# speedPulser.net
KiCad netlist of a schematic drawn in EasyEDA Pro
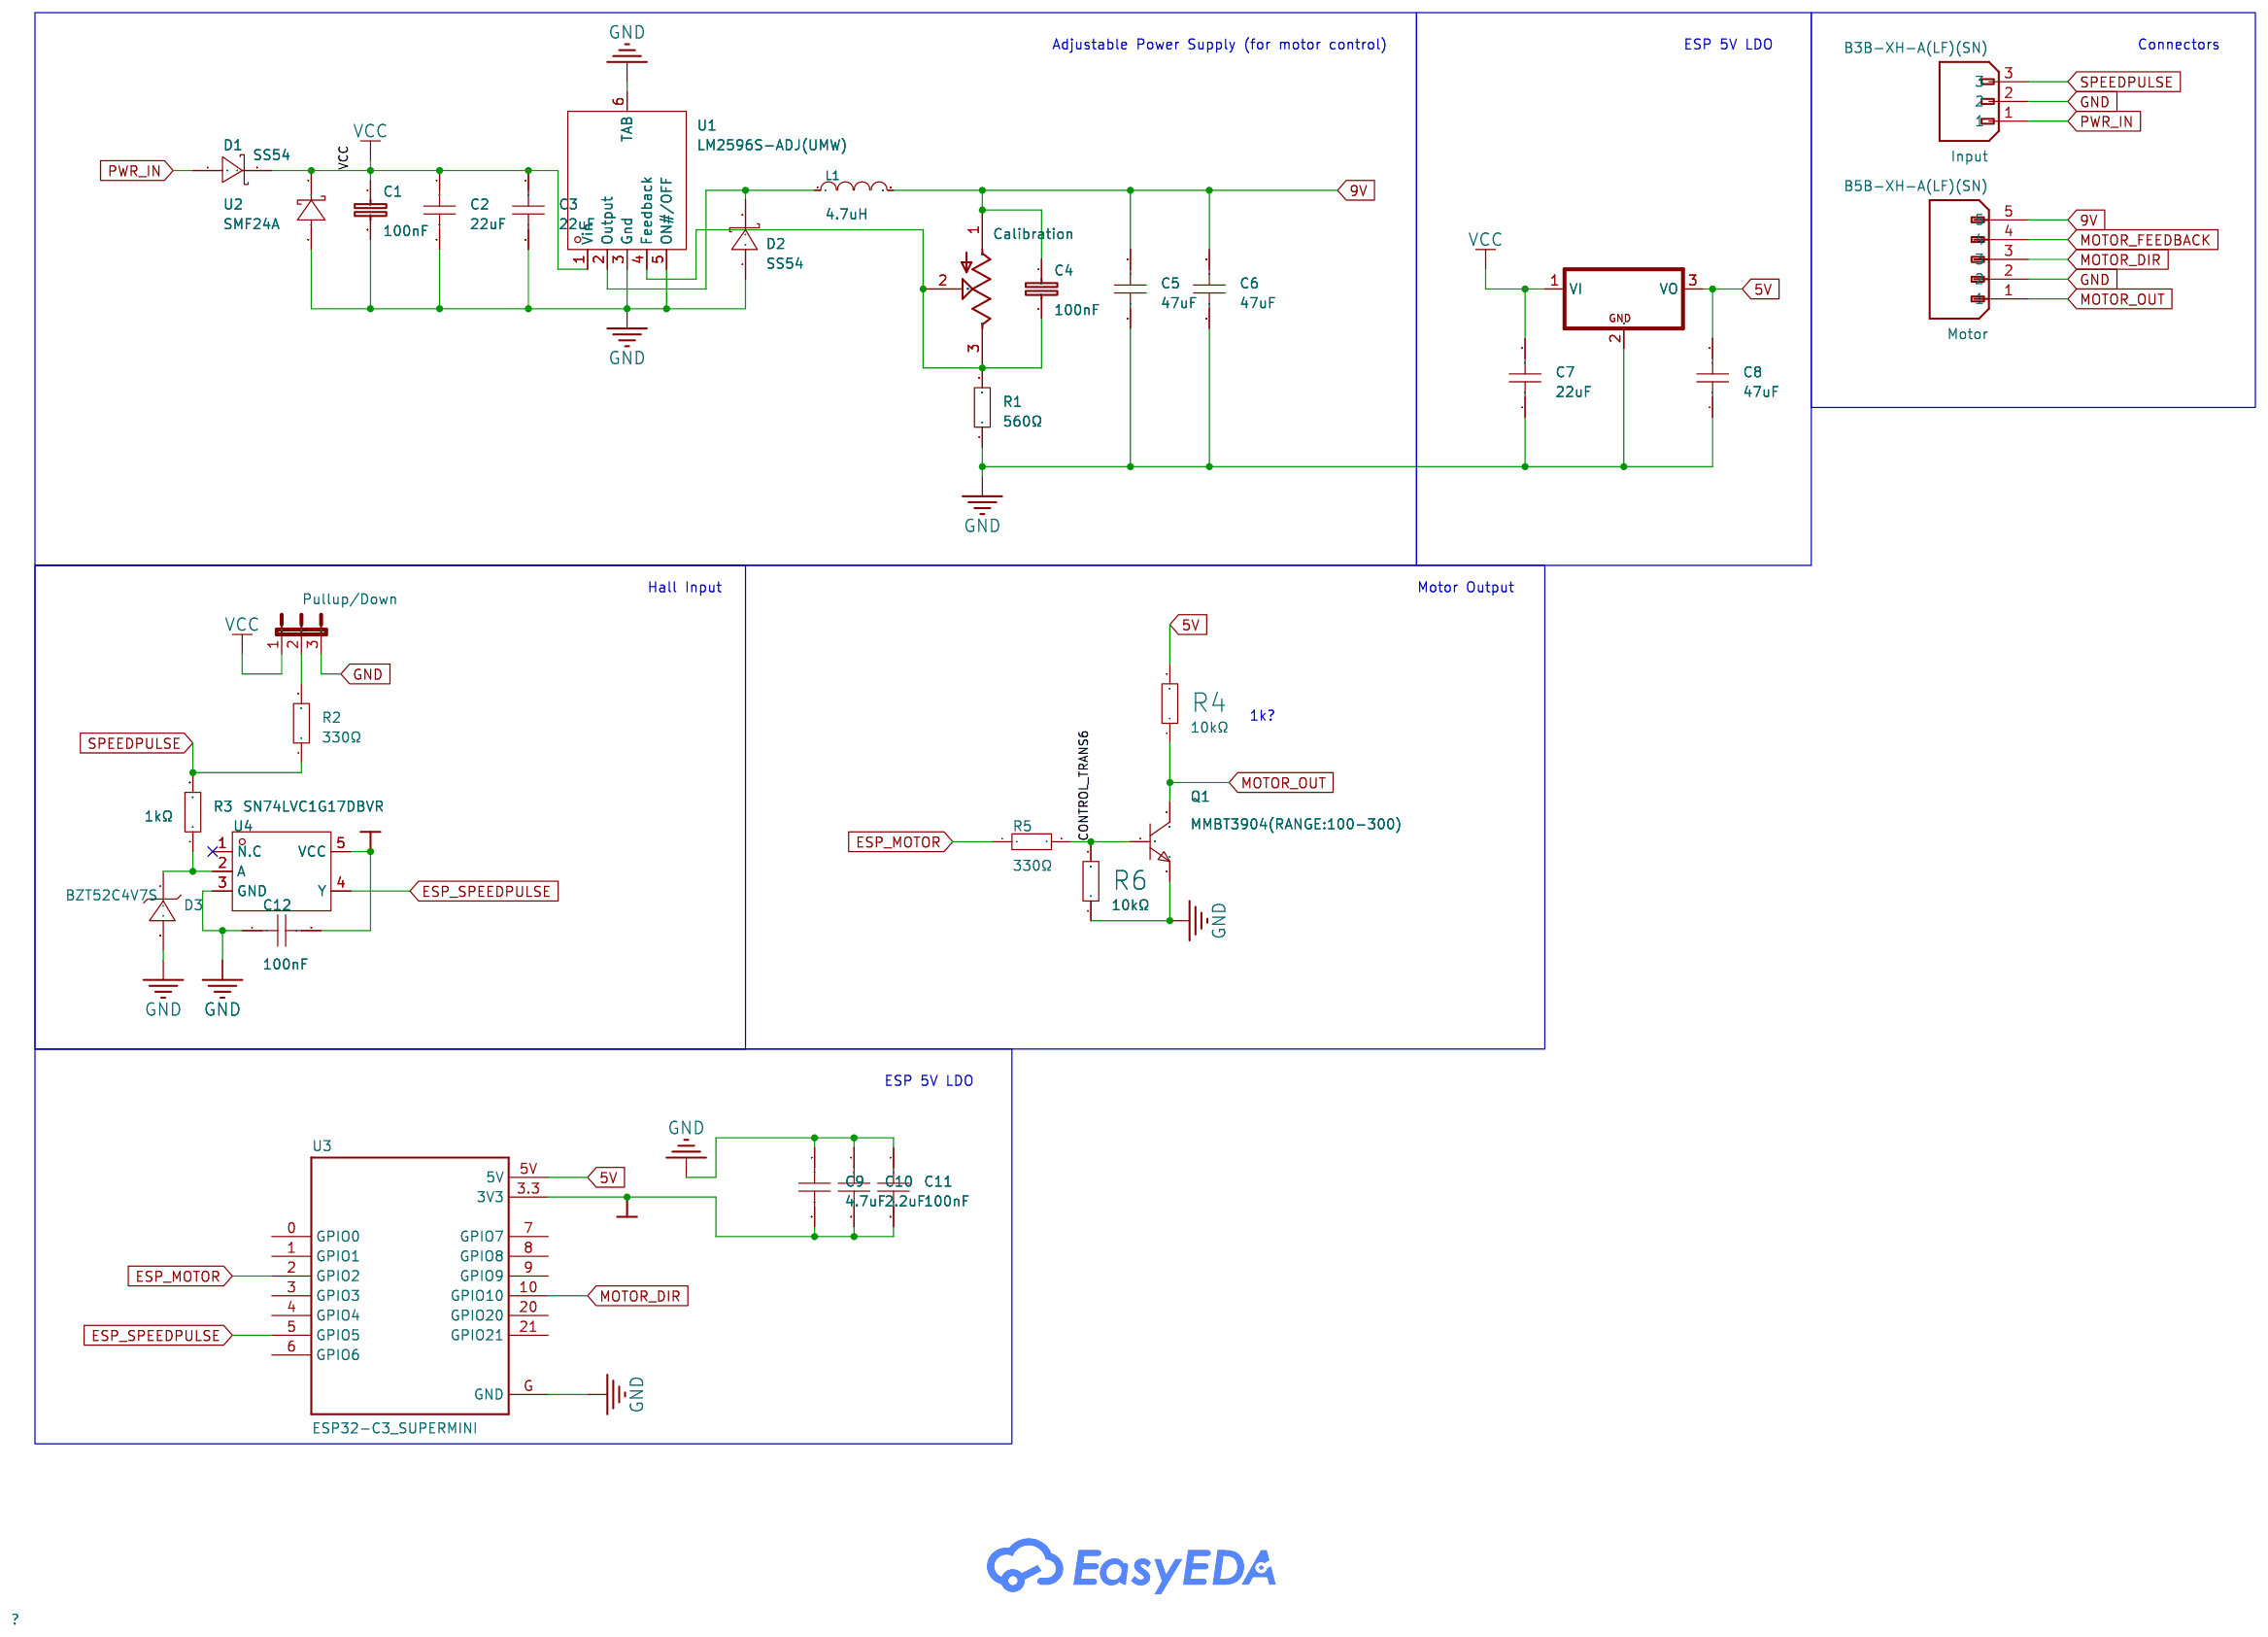
[diagram p0: schematic sheet]

(export (version "E")
  (design (tool "Eeschema 10.0.6"))
  (components
    (comp (ref "C1")
      (value "100nF")
      (description "Capacitance:100nF Tolerance:±10% Tolerance:±10% Voltage Rating:50V Temperature Coefficient:-")
      (fields
        (field (name "Manufacturer Part") "CT41G-0805-2X1-50V-0.1μF-K(N)")
        (field (name "Manufacturer") "TORCH(火炬)")
      )
      (libsource (lib "easyedapro") (part "capacitor-wima_C_2.5/2"))
    )
    (comp (ref "C2")
      (value "22uF")
      (footprint "easyedapro:C0805")
      (fields
        (field (name "Manufacturer Part") "HGC0805R5226M350NSLJ")
        (field (name "Manufacturer") "Chinocera(华瓷)")
      )
      (libsource (lib "easyedapro") (part "HGC0805R5226M350NSLJ"))
    )
    (comp (ref "C3")
      (value "22uF")
      (footprint "easyedapro:C0805")
      (fields
        (field (name "Manufacturer Part") "HGC0805R5226M350NSLJ")
        (field (name "Manufacturer") "Chinocera(华瓷)")
      )
      (libsource (lib "easyedapro") (part "HGC0805R5226M350NSLJ"))
    )
    (comp (ref "C4")
      (value "100nF")
      (description "Capacitance:100nF Tolerance:±10% Tolerance:±10% Voltage Rating:50V Temperature Coefficient:-")
      (fields
        (field (name "Manufacturer Part") "CT41G-0805-2X1-50V-0.1μF-K(N)")
        (field (name "Manufacturer") "TORCH(火炬)")
      )
      (libsource (lib "easyedapro") (part "capacitor-wima_C_2.5/2"))
    )
    (comp (ref "C5")
      (value "47uF")
      (footprint "easyedapro:C0805")
      (description "Capacitance:47uF Tolerance:±20% Tolerance:±20% Voltage Rating:10V Temperature Coefficient:X5R")
      (fields
        (field (name "Manufacturer Part") "CL21A476MPYNNWE")
        (field (name "Manufacturer") "SAMSUNG(三星)")
      )
      (libsource (lib "easyedapro") (part "CL21A476MPYNNWE"))
    )
    (comp (ref "C6")
      (value "47uF")
      (footprint "easyedapro:C0805")
      (description "Capacitance:47uF Tolerance:±20% Tolerance:±20% Voltage Rating:10V Temperature Coefficient:X5R")
      (fields
        (field (name "Manufacturer Part") "CL21A476MPYNNWE")
        (field (name "Manufacturer") "SAMSUNG(三星)")
      )
      (libsource (lib "easyedapro") (part "CL21A476MPYNNWE"))
    )
    (comp (ref "C7")
      (value "22uF")
      (footprint "easyedapro:C0805")
      (fields
        (field (name "Manufacturer Part") "HGC0805R5226M350NSLJ")
        (field (name "Manufacturer") "Chinocera(华瓷)")
      )
      (libsource (lib "easyedapro") (part "HGC0805R5226M350NSLJ"))
    )
    (comp (ref "C8")
      (value "47uF")
      (footprint "easyedapro:C0805")
      (description "Capacitance:47uF Tolerance:±20% Tolerance:±20% Voltage Rating:10V Temperature Coefficient:X5R")
      (fields
        (field (name "Manufacturer Part") "CL21A476MPYNNWE")
        (field (name "Manufacturer") "SAMSUNG(三星)")
      )
      (libsource (lib "easyedapro") (part "CL21A476MPYNNWE"))
    )
    (comp (ref "C9")
      (value "4.7uF")
      (description "Capacitance:4.7uF Tolerance:±10% Tolerance:±10% Voltage Rating:10V Temperature Coefficient:X5R")
      (fields
        (field (name "Manufacturer Part") "CL10A475KP8NNNC")
        (field (name "Manufacturer") "SAMSUNG(三星)")
      )
      (libsource (lib "easyedapro") (part "CAP"))
    )
    (comp (ref "C10")
      (value "2.2uF")
      (description "Capacitance:2.2uF Tolerance:±10% Tolerance:±10% Voltage Rating:16V Temperature Coefficient:X5R")
      (fields
        (field (name "Manufacturer Part") "CL10A225KO8NNNC")
        (field (name "Manufacturer") "SAMSUNG(三星)")
      )
      (libsource (lib "easyedapro") (part "CAP"))
    )
    (comp (ref "C11")
      (value "100nF")
      (description "Capacitance:100nF Tolerance:±10% Tolerance:±10% Voltage Rating:50V Temperature Coefficient:X7R")
      (fields
        (field (name "Manufacturer Part") "CL10B104KB8NNNC")
        (field (name "Manufacturer") "SAMSUNG(三星)")
      )
      (libsource (lib "easyedapro") (part "CAP"))
    )
    (comp (ref "C12")
      (value "100nF")
      (footprint "easyedapro:C0603")
      (description "Capacitance:100nF Tolerance:±10% Tolerance:±10% Voltage Rating:50V Temperature Coefficient:X7R")
      (fields
        (field (name "Manufacturer Part") "CC0603KRX7R9BB104")
        (field (name "Manufacturer") "YAGEO(国巨)")
      )
      (libsource (lib "easyedapro") (part "CC0603KRX7R9BB104"))
    )
    (comp (ref "Calibration")
      (value "10kΩ")
      (description "Resistance: Tolerance:±10% Tolerance:±10%")
      (fields (field (name "Manufacturer Part") "3362P-1-103") (field (name "Manufacturer") "BOCHEN(博晨)"))
      (libsource (lib "easyedapro") (part "3362P-1-253LF_3362P-1-253LF_"))
    )
    (comp (ref "D1")
      (value "SS54")
      (footprint "easyedapro:SMA_L4.4-W2.8-LS5.4-R-RD")
      (fields (field (name "Manufacturer") "MDD(辰达半导体)"))
      (libsource (lib "easyedapro") (part "SS54_C22452"))
    )
    (comp (ref "D2")
      (value "SS54")
      (footprint "easyedapro:SMA_L4.4-W2.8-LS5.4-R-RD")
      (fields (field (name "Manufacturer") "MDD(辰达半导体)"))
      (libsource (lib "easyedapro") (part "SS54_C22452"))
    )
    (comp (ref "D3")
      (value "BZT52C4V7S")
      (footprint "easyedapro:SOD-323_L1.8-W1.3-LS2.5-RD")
      (fields (field (name "Manufacturer") "晶导微电子"))
      (libsource (lib "easyedapro") (part "BZT52C4V7S_C353517"))
    )
    (comp (ref "IC1")
      (value "L7805ABD2T-TR")
      (fields (field (name "Manufacturer") "ST(意法半导体)"))
      (libsource (lib "easyedapro") (part "linear_78*_TV"))
    )
    (comp (ref "Input")
      (value "B3B-XH-A(LF)(SN)")
      (fields (field (name "Manufacturer") "JST"))
      (libsource (lib "easyedapro") (part "B3B-XH-A_LF__SN__B3B-XH-A(LF)(SN)_"))
    )
    (comp (ref "L1")
      (value "4.7uH")
      (footprint "easyedapro:IND-SMD_L4.8-W4.5")
      (fields (field (name "Manufacturer Part") "SMMS0420-4R7M") (field (name "Manufacturer") "SXN(顺翔诺)"))
      (libsource (lib "easyedapro") (part "SMMS0420-4R7M"))
    )
    (comp (ref "Motor")
      (value "B5B-XH-A(LF)(SN)")
      (fields (field (name "Manufacturer") "JST"))
      (libsource (lib "easyedapro") (part "B5B-XH-A_LF__SN__B5B-XH-A(LF)(SN)_"))
    )
    (comp (ref "Pullup/Down")
      (value "PZ254V-11-03P")
      (fields (field (name "Manufacturer") "XFCN(兴飞)"))
      (libsource (lib "easyedapro") (part "jumper_JP2E_"))
    )
    (comp (ref "Q1")
      (value "MMBT3904(RANGE:100-300)")
      (footprint "easyedapro:SOT-23-3_L2.9-W1.3-P1.90-LS2.4-BR")
      (fields (field (name "Manufacturer") "CJ(江苏长电/长晶)"))
      (libsource (lib "easyedapro") (part "MMBT3904"))
    )
    (comp (ref "R1")
      (value "560Ω")
      (footprint "easyedapro:R0603")
      (fields
        (field (name "Manufacturer Part") "0603WAF5600T5E")
        (field (name "Manufacturer") "UNI-ROYAL(厚声)")
      )
      (libsource (lib "easyedapro") (part "0603WAF5600T5E"))
    )
    (comp (ref "R2")
      (value "330Ω")
      (footprint "easyedapro:R0603")
      (fields
        (field (name "Manufacturer Part") "0603WAF3300T5E")
        (field (name "Manufacturer") "UNI-ROYAL(厚声)")
      )
      (libsource (lib "easyedapro") (part "0603WAF3300T5E"))
    )
    (comp (ref "R3")
      (value "1kΩ")
      (footprint "easyedapro:R0603")
      (fields
        (field (name "Manufacturer Part") "0603WAF1001T5E")
        (field (name "Manufacturer") "UNI-ROYAL(厚声)")
      )
      (libsource (lib "easyedapro") (part "0603WAF1001T5E"))
    )
    (comp (ref "R4")
      (value "10kΩ")
      (footprint "easyedapro:R0603")
      (fields
        (field (name "Manufacturer Part") "0603WAF1002T5E")
        (field (name "Manufacturer") "UNI-ROYAL(厚声)")
      )
      (libsource (lib "easyedapro") (part "0603WAF1002T5E"))
    )
    (comp (ref "R5")
      (value "330Ω")
      (footprint "easyedapro:R0603")
      (fields
        (field (name "Manufacturer Part") "0603WAF3300T5E")
        (field (name "Manufacturer") "UNI-ROYAL(厚声)")
      )
      (libsource (lib "easyedapro") (part "0603WAF3300T5E"))
    )
    (comp (ref "R6")
      (value "10kΩ")
      (footprint "easyedapro:R0603")
      (fields
        (field (name "Manufacturer Part") "0603WAF1002T5E")
        (field (name "Manufacturer") "UNI-ROYAL(厚声)")
      )
      (libsource (lib "easyedapro") (part "0603WAF1002T5E"))
    )
    (comp (ref "U1")
      (value "LM2596S-ADJ(UMW)")
      (footprint "easyedapro:TO-263-5_L10.2-W8.9-P1.70-BR")
      (fields (field (name "Manufacturer") "UMW(友台半导体)"))
      (libsource (lib "easyedapro") (part "LM2596S-ADJ"))
    )
    (comp (ref "U2")
      (value "SMF24A")
      (footprint "easyedapro:SOD-123FL_L2.8-W1.8-LS3.7-RD-1")
      (fields (field (name "Manufacturer") "HXY MOSFET(华轩阳电子)"))
      (libsource (lib "easyedapro") (part "SMF24A_C7495269"))
    )
    (comp (ref "U3")
      (value "ESP32-C3_SUPERMINI")
      (footprint "easyedapro:MODULE_ESP32-C3_SUPERMINI")
      (libsource (lib "easyedapro") (part "ESP32-C3_SUPERMINI_ESP32-C3_SUPERMINI_"))
    )
    (comp (ref "U4")
      (value "SN74LVC1G17DBVR")
      (footprint "easyedapro:SOT-23-5_L3.0-W1.5-P0.95-LS2.8-BL")
      (fields (field (name "Manufacturer") "TECH PUBLIC(台舟)"))
      (libsource (lib "easyedapro") (part "SN74LVC1G17DBVR_C19829662"))
    )
  )
  (nets
    (net (code "1") (name "/CONTROL_TRANS6") (class "Default")
      (node (ref "Q1") (pin "1") (pinfunction "B_1") (pintype "unspecified"))
      (node (ref "R5") (pin "2") (pinfunction "2_2") (pintype "input"))
      (node (ref "R6") (pin "2") (pinfunction "2_2") (pintype "input"))
    )
    (net (code "2") (name "3V3") (class "Default")
      (node (ref "C10") (pin "2") (pinfunction "2_2") (pintype "input"))
      (node (ref "C11") (pin "2") (pinfunction "2_2") (pintype "input"))
      (node (ref "C12") (pin "2") (pinfunction "2_2") (pintype "unspecified"))
      (node (ref "C9") (pin "2") (pinfunction "2_2") (pintype "input"))
      (node (ref "U3") (pin "3.3") (pinfunction "3V3_3.3") (pintype "unspecified"))
      (node (ref "U4") (pin "5") (pinfunction "VCC_5") (pintype "unspecified"))
    )
    (net (code "3") (name "5V") (class "Default")
      (node (ref "C8") (pin "2") (pinfunction "2_2") (pintype "unspecified"))
      (node (ref "IC1") (pin "3") (pinfunction "VO_3") (pintype "unspecified"))
      (node (ref "R4") (pin "2") (pinfunction "2_2") (pintype "input"))
      (node (ref "U3") (pin "5V") (pinfunction "5V_5V") (pintype "unspecified"))
    )
    (net (code "4") (name "9V") (class "Default")
      (node (ref "C4") (pin "1") (pinfunction "1_1") (pintype "unspecified"))
      (node (ref "C5") (pin "2") (pinfunction "2_2") (pintype "unspecified"))
      (node (ref "C6") (pin "2") (pinfunction "2_2") (pintype "unspecified"))
      (node (ref "Calibration") (pin "1") (pinfunction "CCW_1") (pintype "unspecified"))
      (node (ref "L1") (pin "2") (pinfunction "2_2") (pintype "input"))
      (node (ref "Motor") (pin "5") (pinfunction "5_5") (pintype "unspecified"))
    )
    (net (code "5") (name "ESP_MOTOR") (class "Default")
      (node (ref "R5") (pin "1") (pinfunction "1_1") (pintype "input"))
      (node (ref "U3") (pin "2") (pinfunction "GPIO2_2") (pintype "bidirectional"))
    )
    (net (code "6") (name "ESP_SPEEDPULSE") (class "Default")
      (node (ref "U3") (pin "5") (pinfunction "GPIO5_5") (pintype "bidirectional"))
      (node (ref "U4") (pin "4") (pinfunction "Y_4") (pintype "unspecified"))
    )
    (net (code "7") (name "GND") (class "Default")
      (node (ref "C1") (pin "2") (pinfunction "2_2") (pintype "unspecified"))
      (node (ref "C10") (pin "1") (pinfunction "1_1") (pintype "input"))
      (node (ref "C11") (pin "1") (pinfunction "1_1") (pintype "input"))
      (node (ref "C12") (pin "1") (pinfunction "1_1") (pintype "unspecified"))
      (node (ref "C2") (pin "2") (pinfunction "2_2") (pintype "unspecified"))
      (node (ref "C3") (pin "2") (pinfunction "2_2") (pintype "unspecified"))
      (node (ref "C5") (pin "1") (pinfunction "1_1") (pintype "unspecified"))
      (node (ref "C6") (pin "1") (pinfunction "1_1") (pintype "unspecified"))
      (node (ref "C7") (pin "1") (pinfunction "1_1") (pintype "unspecified"))
      (node (ref "C8") (pin "1") (pinfunction "1_1") (pintype "unspecified"))
      (node (ref "C9") (pin "1") (pinfunction "1_1") (pintype "input"))
      (node (ref "D2") (pin "1") (pinfunction "A_1") (pintype "unspecified"))
      (node (ref "D3") (pin "2") (pinfunction "A_2") (pintype "unspecified"))
      (node (ref "IC1") (pin "2") (pinfunction "GND_2") (pintype "unspecified"))
      (node (ref "Input") (pin "2") (pinfunction "2_2") (pintype "unspecified"))
      (node (ref "Motor") (pin "2") (pinfunction "2_2") (pintype "unspecified"))
      (node (ref "Pullup/Down") (pin "3") (pinfunction "3_3") (pintype "unspecified"))
      (node (ref "Q1") (pin "2") (pinfunction "E_2") (pintype "unspecified"))
      (node (ref "R1") (pin "1") (pinfunction "1_1") (pintype "input"))
      (node (ref "R6") (pin "1") (pinfunction "1_1") (pintype "input"))
      (node (ref "U1") (pin "3") (pinfunction "Gnd_3") (pintype "unspecified"))
      (node (ref "U1") (pin "5") (pinfunction "ON#/OFF_5") (pintype "unspecified"))
      (node (ref "U1") (pin "6") (pinfunction "TAB_6") (pintype "unspecified"))
      (node (ref "U2") (pin "2") (pinfunction "A_2") (pintype "unspecified"))
      (node (ref "U3") (pin "G") (pinfunction "GND_G") (pintype "unspecified"))
      (node (ref "U4") (pin "3") (pinfunction "GND_3") (pintype "unspecified"))
    )
    (net (code "8") (name "MOTOR_DIR") (class "Default")
      (node (ref "Motor") (pin "3") (pinfunction "3_3") (pintype "unspecified"))
      (node (ref "U3") (pin "10") (pinfunction "GPIO10_10") (pintype "bidirectional"))
    )
    (net (code "9") (name "MOTOR_FEEDBACK") (class "Default")
      (node (ref "Motor") (pin "4") (pinfunction "4_4") (pintype "unspecified"))
    )
    (net (code "10") (name "MOTOR_OUT") (class "Default")
      (node (ref "Motor") (pin "1") (pinfunction "1_1") (pintype "unspecified"))
      (node (ref "Q1") (pin "3") (pinfunction "C_3") (pintype "unspecified"))
      (node (ref "R4") (pin "1") (pinfunction "1_1") (pintype "input"))
    )
    (net (code "11") (name "Net-(Calibration-CW)") (class "Default")
      (node (ref "C4") (pin "2") (pinfunction "2_2") (pintype "unspecified"))
      (node (ref "Calibration") (pin "2") (pinfunction "WIPER_2") (pintype "unspecified"))
      (node (ref "Calibration") (pin "3") (pinfunction "CW_3") (pintype "unspecified"))
      (node (ref "R1") (pin "2") (pinfunction "2_2") (pintype "input"))
      (node (ref "U1") (pin "4") (pinfunction "Feedback_4") (pintype "unspecified"))
    )
    (net (code "12") (name "Net-(D2-K)") (class "Default")
      (node (ref "D2") (pin "2") (pinfunction "K_2") (pintype "unspecified"))
      (node (ref "L1") (pin "1") (pinfunction "1_1") (pintype "input"))
      (node (ref "U1") (pin "2") (pinfunction "Output_2") (pintype "unspecified"))
    )
    (net (code "13") (name "Net-(D3-K)") (class "Default")
      (node (ref "D3") (pin "1") (pinfunction "K_1") (pintype "unspecified"))
      (node (ref "R3") (pin "1") (pinfunction "1_1") (pintype "input"))
      (node (ref "U4") (pin "2") (pinfunction "A_2") (pintype "unspecified"))
    )
    (net (code "14") (name "Net-(Pullup/Down-Pad2)") (class "Default")
      (node (ref "Pullup/Down") (pin "2") (pinfunction "2_2") (pintype "unspecified"))
      (node (ref "R2") (pin "2") (pinfunction "2_2") (pintype "input"))
    )
    (net (code "15") (name "PWR_IN") (class "Default")
      (node (ref "D1") (pin "1") (pinfunction "A_1") (pintype "unspecified"))
      (node (ref "Input") (pin "1") (pinfunction "1_1") (pintype "unspecified"))
    )
    (net (code "16") (name "SPEEDPULSE") (class "Default")
      (node (ref "Input") (pin "3") (pinfunction "3_3") (pintype "unspecified"))
      (node (ref "R2") (pin "1") (pinfunction "1_1") (pintype "input"))
      (node (ref "R3") (pin "2") (pinfunction "2_2") (pintype "input"))
    )
    (net (code "17") (name "VCC") (class "Default")
      (node (ref "C1") (pin "1") (pinfunction "1_1") (pintype "unspecified"))
      (node (ref "C2") (pin "1") (pinfunction "1_1") (pintype "unspecified"))
      (node (ref "C3") (pin "1") (pinfunction "1_1") (pintype "unspecified"))
      (node (ref "C7") (pin "2") (pinfunction "2_2") (pintype "unspecified"))
      (node (ref "D1") (pin "2") (pinfunction "K_2") (pintype "unspecified"))
      (node (ref "IC1") (pin "1") (pinfunction "VI_1") (pintype "input"))
      (node (ref "Pullup/Down") (pin "1") (pinfunction "1_1") (pintype "unspecified"))
      (node (ref "U1") (pin "1") (pinfunction "Vin_1") (pintype "unspecified"))
      (node (ref "U2") (pin "1") (pinfunction "K_1") (pintype "unspecified"))
    )
    (net (code "18") (name "unconnected-(U3-GPIO0-Pad0)") (class "Default")
      (node (ref "U3") (pin "0") (pinfunction "GPIO0_0") (pintype "bidirectional"))
    )
    (net (code "19") (name "unconnected-(U3-GPIO1-Pad1)") (class "Default")
      (node (ref "U3") (pin "1") (pinfunction "GPIO1_1") (pintype "bidirectional"))
    )
    (net (code "20") (name "unconnected-(U3-GPIO3-Pad3)") (class "Default")
      (node (ref "U3") (pin "3") (pinfunction "GPIO3_3") (pintype "bidirectional"))
    )
    (net (code "21") (name "unconnected-(U3-GPIO4-Pad4)") (class "Default")
      (node (ref "U3") (pin "4") (pinfunction "GPIO4_4") (pintype "bidirectional"))
    )
    (net (code "22") (name "unconnected-(U3-GPIO6-Pad6)") (class "Default")
      (node (ref "U3") (pin "6") (pinfunction "GPIO6_6") (pintype "bidirectional"))
    )
    (net (code "23") (name "unconnected-(U3-GPIO7-Pad7)") (class "Default")
      (node (ref "U3") (pin "7") (pinfunction "GPIO7_7") (pintype "bidirectional"))
    )
    (net (code "24") (name "unconnected-(U3-GPIO8-Pad8)") (class "Default")
      (node (ref "U3") (pin "8") (pinfunction "GPIO8_8") (pintype "bidirectional"))
    )
    (net (code "25") (name "unconnected-(U3-GPIO9-Pad9)") (class "Default")
      (node (ref "U3") (pin "9") (pinfunction "GPIO9_9") (pintype "bidirectional"))
    )
    (net (code "26") (name "unconnected-(U3-GPIO20-Pad20)") (class "Default")
      (node (ref "U3") (pin "20") (pinfunction "GPIO20_20") (pintype "bidirectional"))
    )
    (net (code "27") (name "unconnected-(U3-GPIO21-Pad21)") (class "Default")
      (node (ref "U3") (pin "21") (pinfunction "GPIO21_21") (pintype "bidirectional"))
    )
    (net (code "28") (name "unconnected-(U4-N.C-Pad1)") (class "Default")
      (node (ref "U4") (pin "1") (pinfunction "N.C_1") (pintype "unspecified+no_connect"))
    )
  )
)
